# Esquematico.net
KiCad netlist of a schematic drawn in EAGLE
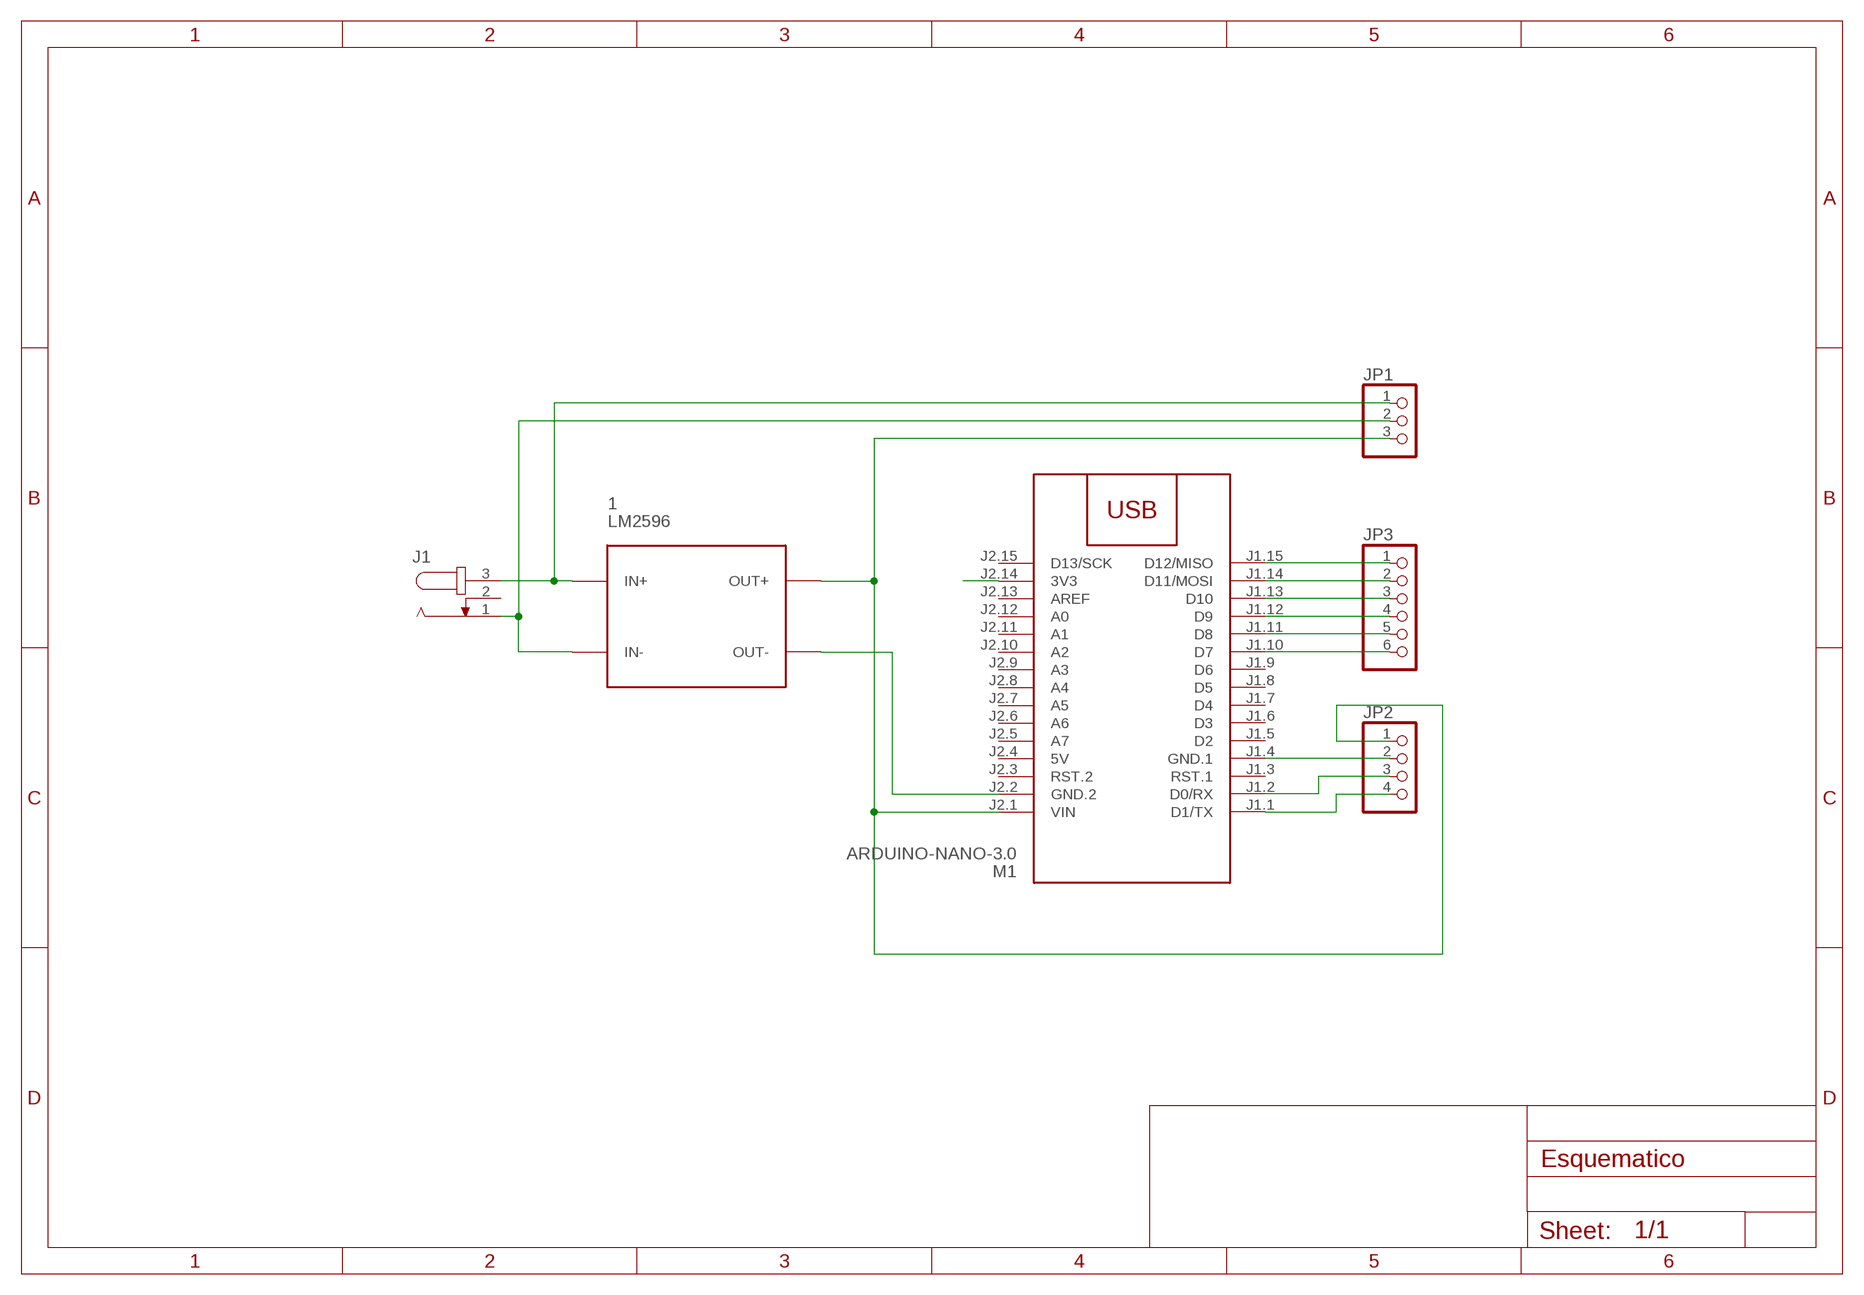
[diagram p0: schematic, sheet 1]

(export (version "E")
  (design (tool "Eeschema 10.0.6"))
  (components
    (comp (ref "1")
      (value "LM2596")
      (footprint "eagle-import:DC-DC-STEP-DOWN-LM2596")
      (libsource (lib "eagle-import") (part "DC-DC-STEP-DOWN-LM2596"))
    )
    (comp (ref "J1")
      (value "JACK-PLUG0")
      (footprint "eagle-import:SPC4077")
      (libsource (lib "eagle-import") (part "JACK-PLUG0"))
    )
    (comp (ref "JP1")
      (value "PINHD-1X3")
      (footprint "eagle-import:1X03")
      (libsource (lib "eagle-import") (part "PINHD-1X3"))
    )
    (comp (ref "JP2")
      (value "PINHD-1X4")
      (footprint "eagle-import:1X04")
      (libsource (lib "eagle-import") (part "PINHD-1X4"))
    )
    (comp (ref "JP3")
      (value "PINHD-1X6")
      (footprint "eagle-import:1X06")
      (libsource (lib "eagle-import") (part "PINHD-1X6"))
    )
    (comp (ref "M1")
      (value "ARDUINO-NANO-3.0")
      (footprint "eagle-import:ARDUINO-NANO-3.0")
      (libsource (lib "eagle-import") (part "ARDUINO-NANO-3.0"))
    )
  )
  (nets
    (net (code "1") (name "/5V") (class "Default")
      (node (ref "M1") (pin "J2.4") (pinfunction "5V_J2.4") (pintype "power_in"))
    )
    (net (code "2") (name "Net-(1-PadIN+)") (class "Default")
      (node (ref "1") (pin "IN+") (pinfunction "IN+_IN+") (pintype "bidirectional"))
      (node (ref "J1") (pin "3") (pinfunction "3_3") (pintype "passive"))
      (node (ref "JP1") (pin "1") (pinfunction "1_1") (pintype "passive"))
    )
    (net (code "3") (name "Net-(1-PadIN-)") (class "Default")
      (node (ref "1") (pin "IN-") (pinfunction "IN-_IN-") (pintype "bidirectional"))
      (node (ref "J1") (pin "1") (pinfunction "1_1") (pintype "passive"))
      (node (ref "JP1") (pin "2") (pinfunction "2_2") (pintype "passive"))
    )
    (net (code "4") (name "Net-(M1-D0{slash}RX)") (class "Default")
      (node (ref "JP2") (pin "3") (pinfunction "3_3") (pintype "passive"))
      (node (ref "M1") (pin "J1.2") (pinfunction "D0/RX_J1.2") (pintype "bidirectional"))
    )
    (net (code "5") (name "Net-(M1-D1{slash}TX)") (class "Default")
      (node (ref "JP2") (pin "4") (pinfunction "4_4") (pintype "passive"))
      (node (ref "M1") (pin "J1.1") (pinfunction "D1/TX_J1.1") (pintype "bidirectional"))
    )
    (net (code "6") (name "Net-(M1-D7)") (class "Default")
      (node (ref "JP3") (pin "6") (pinfunction "6_6") (pintype "passive"))
      (node (ref "M1") (pin "J1.10") (pinfunction "D7_J1.10") (pintype "bidirectional"))
    )
    (net (code "7") (name "Net-(M1-D8)") (class "Default")
      (node (ref "JP3") (pin "5") (pinfunction "5_5") (pintype "passive"))
      (node (ref "M1") (pin "J1.11") (pinfunction "D8_J1.11") (pintype "bidirectional"))
    )
    (net (code "8") (name "Net-(M1-D9)") (class "Default")
      (node (ref "JP3") (pin "4") (pinfunction "4_4") (pintype "passive"))
      (node (ref "M1") (pin "J1.12") (pinfunction "D9_J1.12") (pintype "bidirectional"))
    )
    (net (code "9") (name "Net-(M1-D10)") (class "Default")
      (node (ref "JP3") (pin "3") (pinfunction "3_3") (pintype "passive"))
      (node (ref "M1") (pin "J1.13") (pinfunction "D10_J1.13") (pintype "bidirectional"))
    )
    (net (code "10") (name "Net-(M1-D11{slash}MOSI)") (class "Default")
      (node (ref "JP3") (pin "2") (pinfunction "2_2") (pintype "passive"))
      (node (ref "M1") (pin "J1.14") (pinfunction "D11/MOSI_J1.14") (pintype "bidirectional"))
    )
    (net (code "11") (name "Net-(M1-D12{slash}MISO)") (class "Default")
      (node (ref "JP3") (pin "1") (pinfunction "1_1") (pintype "passive"))
      (node (ref "M1") (pin "J1.15") (pinfunction "D12/MISO_J1.15") (pintype "bidirectional"))
    )
    (net (code "12") (name "Net-(M1-GND.1)") (class "Default")
      (node (ref "JP2") (pin "2") (pinfunction "2_2") (pintype "passive"))
      (node (ref "M1") (pin "J1.4") (pinfunction "GND.1_J1.4") (pintype "power_in"))
    )
    (net (code "13") (name "Net-(M1-GND.2)") (class "Default")
      (node (ref "1") (pin "OUT-") (pinfunction "OUT-_OUT-") (pintype "bidirectional"))
      (node (ref "M1") (pin "J2.2") (pinfunction "GND.2_J2.2") (pintype "power_in"))
    )
    (net (code "14") (name "Net-(M1-VIN)") (class "Default")
      (node (ref "1") (pin "OUT+") (pinfunction "OUT+_OUT+") (pintype "bidirectional"))
      (node (ref "JP1") (pin "3") (pinfunction "3_3") (pintype "passive"))
      (node (ref "JP2") (pin "1") (pinfunction "1_1") (pintype "passive"))
      (node (ref "M1") (pin "J2.1") (pinfunction "VIN_J2.1") (pintype "power_in"))
    )
    (net (code "15") (name "unconnected-(J1-Pad2)") (class "Default")
      (node (ref "J1") (pin "2") (pinfunction "2_2") (pintype "passive"))
    )
    (net (code "16") (name "unconnected-(M1-3V3-PadJ2.14)") (class "Default")
      (node (ref "M1") (pin "J2.14") (pinfunction "3V3_J2.14") (pintype "power_in"))
    )
    (net (code "17") (name "unconnected-(M1-A0-PadJ2.12)") (class "Default")
      (node (ref "M1") (pin "J2.12") (pinfunction "A0_J2.12") (pintype "bidirectional"))
    )
    (net (code "18") (name "unconnected-(M1-A1-PadJ2.11)") (class "Default")
      (node (ref "M1") (pin "J2.11") (pinfunction "A1_J2.11") (pintype "bidirectional"))
    )
    (net (code "19") (name "unconnected-(M1-A2-PadJ2.10)") (class "Default")
      (node (ref "M1") (pin "J2.10") (pinfunction "A2_J2.10") (pintype "bidirectional"))
    )
    (net (code "20") (name "unconnected-(M1-A3-PadJ2.9)") (class "Default")
      (node (ref "M1") (pin "J2.9") (pinfunction "A3_J2.9") (pintype "bidirectional"))
    )
    (net (code "21") (name "unconnected-(M1-A4-PadJ2.8)") (class "Default")
      (node (ref "M1") (pin "J2.8") (pinfunction "A4_J2.8") (pintype "bidirectional"))
    )
    (net (code "22") (name "unconnected-(M1-A5-PadJ2.7)") (class "Default")
      (node (ref "M1") (pin "J2.7") (pinfunction "A5_J2.7") (pintype "bidirectional"))
    )
    (net (code "23") (name "unconnected-(M1-A6-PadJ2.6)") (class "Default")
      (node (ref "M1") (pin "J2.6") (pinfunction "A6_J2.6") (pintype "bidirectional"))
    )
    (net (code "24") (name "unconnected-(M1-A7-PadJ2.5)") (class "Default")
      (node (ref "M1") (pin "J2.5") (pinfunction "A7_J2.5") (pintype "bidirectional"))
    )
    (net (code "25") (name "unconnected-(M1-AREF-PadJ2.13)") (class "Default")
      (node (ref "M1") (pin "J2.13") (pinfunction "AREF_J2.13") (pintype "bidirectional"))
    )
    (net (code "26") (name "unconnected-(M1-D2-PadJ1.5)") (class "Default")
      (node (ref "M1") (pin "J1.5") (pinfunction "D2_J1.5") (pintype "bidirectional"))
    )
    (net (code "27") (name "unconnected-(M1-D3-PadJ1.6)") (class "Default")
      (node (ref "M1") (pin "J1.6") (pinfunction "D3_J1.6") (pintype "bidirectional"))
    )
    (net (code "28") (name "unconnected-(M1-D4-PadJ1.7)") (class "Default")
      (node (ref "M1") (pin "J1.7") (pinfunction "D4_J1.7") (pintype "bidirectional"))
    )
    (net (code "29") (name "unconnected-(M1-D5-PadJ1.8)") (class "Default")
      (node (ref "M1") (pin "J1.8") (pinfunction "D5_J1.8") (pintype "bidirectional"))
    )
    (net (code "30") (name "unconnected-(M1-D6-PadJ1.9)") (class "Default")
      (node (ref "M1") (pin "J1.9") (pinfunction "D6_J1.9") (pintype "bidirectional"))
    )
    (net (code "31") (name "unconnected-(M1-D13{slash}SCK-PadJ2.15)") (class "Default")
      (node (ref "M1") (pin "J2.15") (pinfunction "D13/SCK_J2.15") (pintype "bidirectional"))
    )
    (net (code "32") (name "unconnected-(M1-RST.1-PadJ1.3)") (class "Default")
      (node (ref "M1") (pin "J1.3") (pinfunction "RST.1_J1.3") (pintype "bidirectional"))
    )
    (net (code "33") (name "unconnected-(M1-RST.2-PadJ2.3)") (class "Default")
      (node (ref "M1") (pin "J2.3") (pinfunction "RST.2_J2.3") (pintype "bidirectional"))
    )
  )
)
